# easy-eda-project.net
KiCad netlist of a schematic drawn in EasyEDA
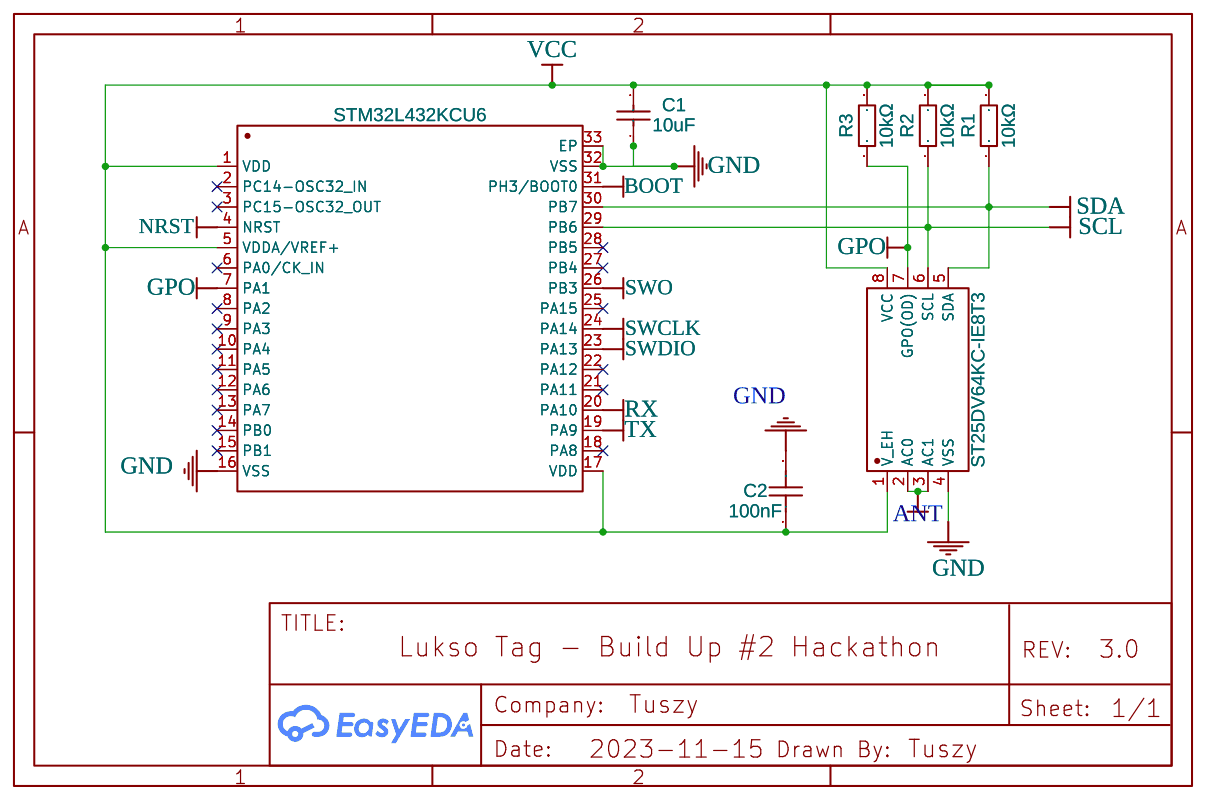
[diagram p0: schematic sheet]

(export (version "E")
  (design (tool "Eeschema 10.0.6"))
  (components
    (comp (ref "C1")
      (value "10uF")
      (fields
        (field (name "Manufacturer Part") "CL05A106MQ5NUNC")
        (field (name "Manufacturer") "SAMSUNG(三星)")
      )
      (libsource (lib "") (part "CL05A106MQ5NUNC"))
    )
    (comp (ref "C2")
      (value "100nF")
      (fields
        (field (name "Manufacturer Part") "CC0402JRX7R7BB104")
        (field (name "Manufacturer") "YAGEO(国巨)")
      )
      (libsource (lib "") (part "CC0402JRX7R7BB104"))
    )
    (comp (ref "R1")
      (value "10kΩ")
      (fields
        (field (name "Manufacturer Part") "0402WGF1002TCE")
        (field (name "Manufacturer") "UNI-ROYAL(厚声)")
      )
      (libsource (lib "") (part "0402WGF1002TCE"))
    )
    (comp (ref "R2")
      (value "10kΩ")
      (fields
        (field (name "Manufacturer Part") "0402WGF1002TCE")
        (field (name "Manufacturer") "UNI-ROYAL(厚声)")
      )
      (libsource (lib "") (part "0402WGF1002TCE"))
    )
    (comp (ref "R3")
      (value "10kΩ")
      (fields
        (field (name "Manufacturer Part") "0402WGF1002TCE")
        (field (name "Manufacturer") "UNI-ROYAL(厚声)")
      )
      (libsource (lib "") (part "0402WGF1002TCE"))
    )
    (comp (ref "U1")
      (value "STM32L432KCU6")
      (fields (field (name "Manufacturer") "ST(意法半导体)"))
      (libsource (lib "") (part "STM32L432KCU6"))
    )
    (comp (ref "U3")
      (value "ST25DV64KC-IE8T3")
      (fields (field (name "Manufacturer") "ST(意法半导体)"))
      (libsource (lib "") (part "ST25DV64KC-IE8T3"))
    )
  )
  (nets
    (net (code "1") (name "ANT") (class "Default")
      (node (ref "U3") (pin "2") (pinfunction "AC0_2") (pintype "unspecified"))
      (node (ref "U3") (pin "3") (pinfunction "AC1_3") (pintype "unspecified"))
    )
    (net (code "2") (name "BOOT") (class "Default")
      (node (ref "U1") (pin "31") (pinfunction "PH3/BOOT0_31") (pintype "unspecified"))
    )
    (net (code "3") (name "GND") (class "Default")
      (node (ref "C1") (pin "1") (pinfunction "1_1") (pintype "input"))
      (node (ref "C2") (pin "2") (pinfunction "2_2") (pintype "unspecified"))
      (node (ref "U1") (pin "16") (pinfunction "VSS_16") (pintype "unspecified"))
      (node (ref "U1") (pin "32") (pinfunction "VSS_32") (pintype "unspecified"))
      (node (ref "U1") (pin "33") (pinfunction "EP_33") (pintype "unspecified"))
      (node (ref "U3") (pin "4") (pinfunction "VSS_4") (pintype "unspecified"))
    )
    (net (code "4") (name "GPO") (class "Default")
      (node (ref "R3") (pin "1") (pinfunction "1_1") (pintype "input"))
      (node (ref "U1") (pin "7") (pinfunction "PA1_7") (pintype "unspecified"))
      (node (ref "U3") (pin "7") (pinfunction "GPO(OD)_7") (pintype "unspecified"))
    )
    (net (code "5") (name "NRST") (class "Default")
      (node (ref "U1") (pin "4") (pinfunction "NRST_4") (pintype "unspecified"))
    )
    (net (code "6") (name "RX") (class "Default")
      (node (ref "U1") (pin "20") (pinfunction "PA10_20") (pintype "unspecified"))
    )
    (net (code "7") (name "SCL") (class "Default")
      (node (ref "R2") (pin "1") (pinfunction "1_1") (pintype "input"))
      (node (ref "U1") (pin "29") (pinfunction "PB6_29") (pintype "unspecified"))
      (node (ref "U3") (pin "6") (pinfunction "SCL_6") (pintype "unspecified"))
    )
    (net (code "8") (name "SDA") (class "Default")
      (node (ref "R1") (pin "1") (pinfunction "1_1") (pintype "input"))
      (node (ref "U1") (pin "30") (pinfunction "PB7_30") (pintype "unspecified"))
      (node (ref "U3") (pin "5") (pinfunction "SDA_5") (pintype "unspecified"))
    )
    (net (code "9") (name "SWCLK") (class "Default")
      (node (ref "U1") (pin "24") (pinfunction "PA14_24") (pintype "unspecified"))
    )
    (net (code "10") (name "SWDIO") (class "Default")
      (node (ref "U1") (pin "23") (pinfunction "PA13_23") (pintype "unspecified"))
    )
    (net (code "11") (name "SWO") (class "Default")
      (node (ref "U1") (pin "26") (pinfunction "PB3_26") (pintype "unspecified"))
    )
    (net (code "12") (name "TX") (class "Default")
      (node (ref "U1") (pin "19") (pinfunction "PA9_19") (pintype "unspecified"))
    )
    (net (code "13") (name "VCC") (class "Default")
      (node (ref "C1") (pin "2") (pinfunction "2_2") (pintype "input"))
      (node (ref "C2") (pin "1") (pinfunction "1_1") (pintype "unspecified"))
      (node (ref "R1") (pin "2") (pinfunction "2_2") (pintype "input"))
      (node (ref "R2") (pin "2") (pinfunction "2_2") (pintype "input"))
      (node (ref "R3") (pin "2") (pinfunction "2_2") (pintype "input"))
      (node (ref "U1") (pin "1") (pinfunction "VDD_1") (pintype "unspecified"))
      (node (ref "U1") (pin "17") (pinfunction "VDD_17") (pintype "unspecified"))
      (node (ref "U1") (pin "5") (pinfunction "VDDA/VREF+_5") (pintype "unspecified"))
      (node (ref "U3") (pin "1") (pinfunction "V_EH_1") (pintype "unspecified"))
      (node (ref "U3") (pin "8") (pinfunction "VCC_8") (pintype "unspecified"))
    )
    (net (code "14") (name "unconnected-(U1-PA0{slash}CK_IN-Pad6)") (class "Default")
      (node (ref "U1") (pin "6") (pinfunction "PA0/CK_IN_6") (pintype "unspecified+no_connect"))
    )
    (net (code "15") (name "unconnected-(U1-PA2-Pad8)") (class "Default")
      (node (ref "U1") (pin "8") (pinfunction "PA2_8") (pintype "unspecified+no_connect"))
    )
    (net (code "16") (name "unconnected-(U1-PA3-Pad9)") (class "Default")
      (node (ref "U1") (pin "9") (pinfunction "PA3_9") (pintype "unspecified+no_connect"))
    )
    (net (code "17") (name "unconnected-(U1-PA4-Pad10)") (class "Default")
      (node (ref "U1") (pin "10") (pinfunction "PA4_10") (pintype "unspecified+no_connect"))
    )
    (net (code "18") (name "unconnected-(U1-PA5-Pad11)") (class "Default")
      (node (ref "U1") (pin "11") (pinfunction "PA5_11") (pintype "unspecified+no_connect"))
    )
    (net (code "19") (name "unconnected-(U1-PA6-Pad12)") (class "Default")
      (node (ref "U1") (pin "12") (pinfunction "PA6_12") (pintype "unspecified+no_connect"))
    )
    (net (code "20") (name "unconnected-(U1-PA7-Pad13)") (class "Default")
      (node (ref "U1") (pin "13") (pinfunction "PA7_13") (pintype "unspecified+no_connect"))
    )
    (net (code "21") (name "unconnected-(U1-PA8-Pad18)") (class "Default")
      (node (ref "U1") (pin "18") (pinfunction "PA8_18") (pintype "unspecified+no_connect"))
    )
    (net (code "22") (name "unconnected-(U1-PA11-Pad21)") (class "Default")
      (node (ref "U1") (pin "21") (pinfunction "PA11_21") (pintype "unspecified+no_connect"))
    )
    (net (code "23") (name "unconnected-(U1-PA12-Pad22)") (class "Default")
      (node (ref "U1") (pin "22") (pinfunction "PA12_22") (pintype "unspecified+no_connect"))
    )
    (net (code "24") (name "unconnected-(U1-PA15-Pad25)") (class "Default")
      (node (ref "U1") (pin "25") (pinfunction "PA15_25") (pintype "unspecified+no_connect"))
    )
    (net (code "25") (name "unconnected-(U1-PB0-Pad14)") (class "Default")
      (node (ref "U1") (pin "14") (pinfunction "PB0_14") (pintype "unspecified+no_connect"))
    )
    (net (code "26") (name "unconnected-(U1-PB1-Pad15)") (class "Default")
      (node (ref "U1") (pin "15") (pinfunction "PB1_15") (pintype "unspecified+no_connect"))
    )
    (net (code "27") (name "unconnected-(U1-PB4-Pad27)") (class "Default")
      (node (ref "U1") (pin "27") (pinfunction "PB4_27") (pintype "unspecified+no_connect"))
    )
    (net (code "28") (name "unconnected-(U1-PB5-Pad28)") (class "Default")
      (node (ref "U1") (pin "28") (pinfunction "PB5_28") (pintype "unspecified+no_connect"))
    )
    (net (code "29") (name "unconnected-(U1-PC14-OSC32_IN-Pad2)") (class "Default")
      (node (ref "U1") (pin "2") (pinfunction "PC14-OSC32_IN_2") (pintype "unspecified+no_connect"))
    )
    (net (code "30") (name "unconnected-(U1-PC15-OSC32_OUT-Pad3)") (class "Default")
      (node (ref "U1") (pin "3") (pinfunction "PC15-OSC32_OUT_3") (pintype "unspecified+no_connect"))
    )
  )
)
